# 10_RK3568_PowerGND.net
KiCad netlist of a schematic drawn in Altium Designer
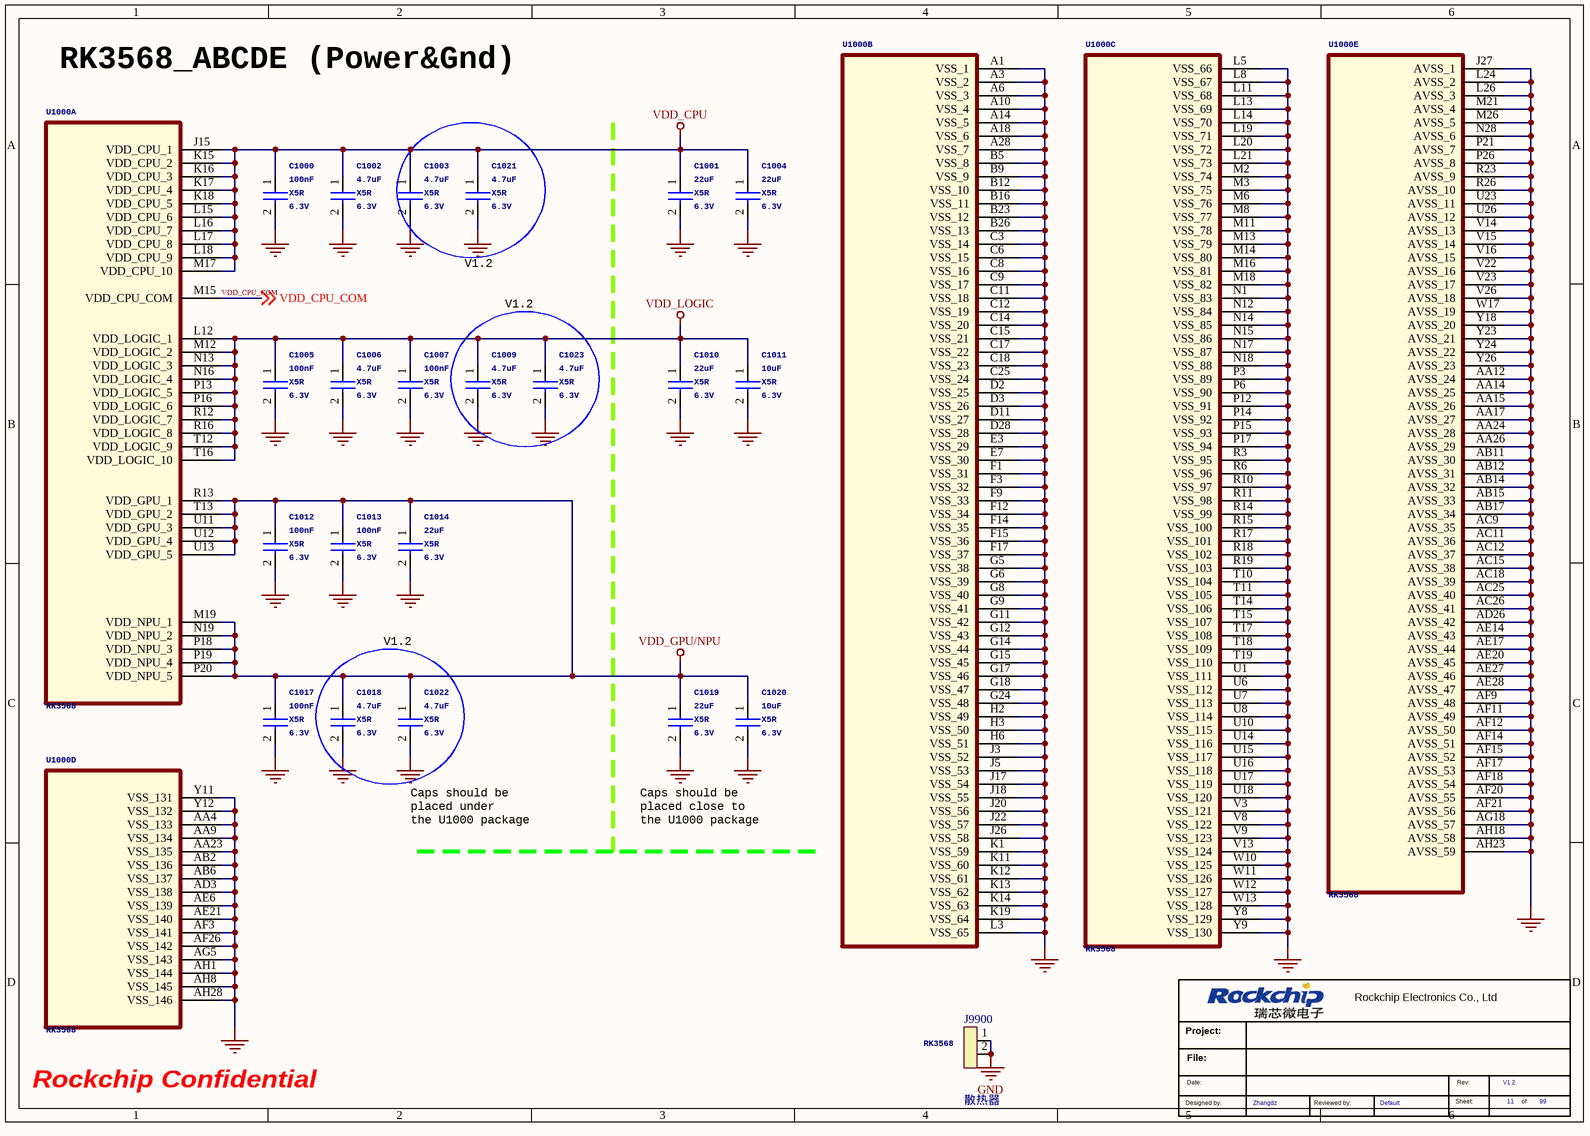
[diagram p0: 10.RK3568_PowerGND.SchDoc]

(export (version "E")
  (design (tool "Eeschema 10.0.6"))
  (components
    (comp (ref "*")
      (value "Rockchip_new")
      (fields
        (field (name "SCHEMATIC PAGE COUNT") "99")
        (field (name "SCHEMATIC PAGE NUMBER") "11")
        (field (name "DESIGNER") "Zhangdz")
        (field (name "REVISION") "V1.2")
        (field (name "CHECK") "Default")
      )
      (libsource (lib "*") (part "Rockchip_new"))
    )
    (comp (ref "C1000")
      (value "100nF")
      (footprint "C0201")
      (description "cap,100.00nF,+/-10%,6.3V,X5R,C0201")
      (fields
        (field (name "VOLTAGE") "6.3V")
        (field (name "DIELECTRIC") "X5R")
        (field (name "TOLERANCE") "10%")
        (field (name "MANUFACTURER") "TDK")
        (field (name "CREATED BY") "JJJ")
      )
      (libsource (lib "*") (part "CAP NP"))
    )
    (comp (ref "C1001")
      (value "22uF")
      (footprint "C0603")
      (description "cap,22.00uF,+/-20%,6.3V,X5R,C0603")
      (fields
        (field (name "VOLTAGE") "6.3V")
        (field (name "DIELECTRIC") "X5R")
        (field (name "TOLERANCE") "20%")
        (field (name "MANUFACTURER") "TDK")
        (field (name "CREATED BY") "JJJ")
      )
      (libsource (lib "*") (part "CAP NP"))
    )
    (comp (ref "C1002")
      (value "4.7uF")
      (footprint "C0402")
      (description "cap,4.70uF,+/-10%,6.3V,X5R,C0402")
      (fields
        (field (name "VOLTAGE") "6.3V")
        (field (name "DIELECTRIC") "X5R")
        (field (name "MANUFACTURER") "TDK")
        (field (name "TOLERANCE") "10%")
        (field (name "CREATED BY") "JJJ")
      )
      (libsource (lib "*") (part "CAP NP"))
    )
    (comp (ref "C1003")
      (value "4.7uF")
      (footprint "C0402")
      (description "cap,4.70uF,+/-10%,6.3V,X5R,C0402")
      (fields
        (field (name "VOLTAGE") "6.3V")
        (field (name "DIELECTRIC") "X5R")
        (field (name "MANUFACTURER") "TDK")
        (field (name "TOLERANCE") "10%")
        (field (name "CREATED BY") "JJJ")
      )
      (libsource (lib "*") (part "CAP NP"))
    )
    (comp (ref "C1004")
      (value "22uF")
      (footprint "C0603")
      (description "cap,22.00uF,+/-20%,6.3V,X5R,C0603")
      (fields
        (field (name "VOLTAGE") "6.3V")
        (field (name "DIELECTRIC") "X5R")
        (field (name "TOLERANCE") "20%")
        (field (name "MANUFACTURER") "TDK")
        (field (name "CREATED BY") "JJJ")
      )
      (libsource (lib "*") (part "CAP NP"))
    )
    (comp (ref "C1005")
      (value "100nF")
      (footprint "C0201")
      (description "cap,100.00nF,+/-10%,6.3V,X5R,C0201")
      (fields
        (field (name "VOLTAGE") "6.3V")
        (field (name "DIELECTRIC") "X5R")
        (field (name "TOLERANCE") "10%")
        (field (name "MANUFACTURER") "TDK")
        (field (name "CREATED BY") "JJJ")
      )
      (libsource (lib "*") (part "CAP NP"))
    )
    (comp (ref "C1006")
      (value "4.7uF")
      (footprint "C0402")
      (description "cap,4.70uF,+/-10%,6.3V,X5R,C0402")
      (fields
        (field (name "VOLTAGE") "6.3V")
        (field (name "DIELECTRIC") "X5R")
        (field (name "MANUFACTURER") "TDK")
        (field (name "TOLERANCE") "10%")
        (field (name "CREATED BY") "JJJ")
      )
      (libsource (lib "*") (part "CAP NP"))
    )
    (comp (ref "C1007")
      (value "100nF")
      (footprint "C0201")
      (description "cap,100.00nF,+/-10%,6.3V,X5R,C0201")
      (fields
        (field (name "VOLTAGE") "6.3V")
        (field (name "DIELECTRIC") "X5R")
        (field (name "TOLERANCE") "10%")
        (field (name "MANUFACTURER") "TDK")
        (field (name "CREATED BY") "JJJ")
      )
      (libsource (lib "*") (part "CAP NP"))
    )
    (comp (ref "C1009")
      (value "4.7uF")
      (footprint "C0402")
      (description "cap,4.70uF,+/-10%,6.3V,X5R,C0402")
      (fields
        (field (name "VOLTAGE") "6.3V")
        (field (name "DIELECTRIC") "X5R")
        (field (name "MANUFACTURER") "TDK")
        (field (name "TOLERANCE") "10%")
        (field (name "CREATED BY") "JJJ")
      )
      (libsource (lib "*") (part "CAP NP"))
    )
    (comp (ref "C1010")
      (value "22uF")
      (footprint "C0603")
      (description "cap,22.00uF,+/-20%,6.3V,X5R,C0603")
      (fields
        (field (name "VOLTAGE") "6.3V")
        (field (name "DIELECTRIC") "X5R")
        (field (name "MANUFACTURER") "TDK")
        (field (name "TOLERANCE") "20%")
        (field (name "CREATED BY") "JJJ")
      )
      (libsource (lib "*") (part "CAP NP"))
    )
    (comp (ref "C1011")
      (value "10uF")
      (footprint "C0603")
      (description "cap,10.00uF,+/-10%,6.3V,X5R,C0603")
      (fields
        (field (name "VOLTAGE") "6.3V")
        (field (name "DIELECTRIC") "X5R")
        (field (name "MANUFACTURER") "TDK")
        (field (name "TOLERANCE") "10%")
        (field (name "CREATED BY") "JJJ")
      )
      (libsource (lib "*") (part "CAP NP"))
    )
    (comp (ref "C1012")
      (value "100nF")
      (footprint "C0201")
      (description "cap,100.00nF,+/-10%,6.3V,X5R,C0201")
      (fields
        (field (name "VOLTAGE") "6.3V")
        (field (name "DIELECTRIC") "X5R")
        (field (name "MANUFACTURER") "TDK")
        (field (name "TOLERANCE") "10%")
        (field (name "CREATED BY") "JJJ")
      )
      (libsource (lib "*") (part "CAP NP"))
    )
    (comp (ref "C1013")
      (value "100nF")
      (footprint "C0201")
      (description "cap,100.00nF,+/-10%,6.3V,X5R,C0201")
      (fields
        (field (name "VOLTAGE") "6.3V")
        (field (name "DIELECTRIC") "X5R")
        (field (name "TOLERANCE") "10%")
        (field (name "MANUFACTURER") "TDK")
        (field (name "CREATED BY") "JJJ")
      )
      (libsource (lib "*") (part "CAP NP"))
    )
    (comp (ref "C1014")
      (value "22uF")
      (footprint "C0603")
      (description "cap,22.00uF,+/-20%,6.3V,X5R,C0603")
      (fields
        (field (name "VOLTAGE") "6.3V")
        (field (name "DIELECTRIC") "X5R")
        (field (name "MANUFACTURER") "TDK")
        (field (name "TOLERANCE") "20%")
        (field (name "CREATED BY") "JJJ")
      )
      (libsource (lib "*") (part "CAP NP"))
    )
    (comp (ref "C1017")
      (value "100nF")
      (footprint "C0201")
      (description "cap,100.00nF,+/-10%,6.3V,X5R,C0201")
      (fields
        (field (name "VOLTAGE") "6.3V")
        (field (name "DIELECTRIC") "X5R")
        (field (name "MANUFACTURER") "TDK")
        (field (name "TOLERANCE") "10%")
        (field (name "CREATED BY") "JJJ")
      )
      (libsource (lib "*") (part "CAP NP"))
    )
    (comp (ref "C1018")
      (value "4.7uF")
      (footprint "C0402")
      (description "cap,4.70uF,+/-10%,6.3V,X5R,C0402")
      (fields
        (field (name "VOLTAGE") "6.3V")
        (field (name "DIELECTRIC") "X5R")
        (field (name "TOLERANCE") "10%")
        (field (name "MANUFACTURER") "TDK")
        (field (name "CREATED BY") "JJJ")
      )
      (libsource (lib "*") (part "CAP NP"))
    )
    (comp (ref "C1019")
      (value "22uF")
      (footprint "C0603")
      (description "cap,22.00uF,+/-20%,6.3V,X5R,C0603")
      (fields
        (field (name "VOLTAGE") "6.3V")
        (field (name "DIELECTRIC") "X5R")
        (field (name "MANUFACTURER") "TDK")
        (field (name "TOLERANCE") "20%")
        (field (name "CREATED BY") "JJJ")
      )
      (libsource (lib "*") (part "CAP NP"))
    )
    (comp (ref "C1020")
      (value "10uF")
      (footprint "C0603")
      (description "cap,10.00uF,+/-10%,6.3V,X5R,C0603")
      (fields
        (field (name "VOLTAGE") "6.3V")
        (field (name "DIELECTRIC") "X5R")
        (field (name "MANUFACTURER") "TDK")
        (field (name "TOLERANCE") "10%")
        (field (name "CREATED BY") "JJJ")
      )
      (libsource (lib "*") (part "CAP NP"))
    )
    (comp (ref "C1021")
      (value "4.7uF")
      (footprint "C0402")
      (description "cap,4.70uF,+/-10%,6.3V,X5R,C0402")
      (fields
        (field (name "VOLTAGE") "6.3V")
        (field (name "DIELECTRIC") "X5R")
        (field (name "MANUFACTURER") "TDK")
        (field (name "TOLERANCE") "10%")
        (field (name "CREATED BY") "JJJ")
      )
      (libsource (lib "*") (part "CAP NP"))
    )
    (comp (ref "C1022")
      (value "4.7uF")
      (footprint "C0402")
      (description "cap,4.70uF,+/-10%,6.3V,X5R,C0402")
      (fields
        (field (name "VOLTAGE") "6.3V")
        (field (name "DIELECTRIC") "X5R")
        (field (name "TOLERANCE") "10%")
        (field (name "MANUFACTURER") "TDK")
        (field (name "CREATED BY") "JJJ")
      )
      (libsource (lib "*") (part "CAP NP"))
    )
    (comp (ref "C1023")
      (value "4.7uF")
      (footprint "C0402")
      (description "cap,4.70uF,+/-10%,6.3V,X5R,C0402")
      (fields
        (field (name "VOLTAGE") "6.3V")
        (field (name "DIELECTRIC") "X5R")
        (field (name "MANUFACTURER") "TDK")
        (field (name "TOLERANCE") "10%")
        (field (name "CREATED BY") "JJJ")
      )
      (libsource (lib "*") (part "CAP NP"))
    )
    (comp (ref "J9900")
      (value "散热器")
      (footprint "RADIATOR_38RX38RX10R")
      (description "SOCKET")
      (libsource (lib "模拟器件") (part "CON2"))
    )
    (comp (ref "U1000")
      (value "RK3568")
      (footprint "BGA636_19R00X19R00X1R20")
      (description "ROCKCHIP SOC")
      (fields (field (name "MANUFACTURER") "Rockchip (瑞芯微)") (field (name "CREATED BY") "JJJ"))
      (libsource (lib "*") (part "SOC_RK3568"))
    )
  )
  (nets
    (net (code "1") (name "GND") (class "Default")
      (node (ref "C1000") (pin "2") (pinfunction "2_2") (pintype "passive"))
      (node (ref "C1001") (pin "2") (pinfunction "2_2") (pintype "passive"))
      (node (ref "C1002") (pin "2") (pinfunction "2_2") (pintype "passive"))
      (node (ref "C1003") (pin "2") (pinfunction "2_2") (pintype "passive"))
      (node (ref "C1004") (pin "2") (pinfunction "2_2") (pintype "passive"))
      (node (ref "C1005") (pin "2") (pinfunction "2_2") (pintype "passive"))
      (node (ref "C1006") (pin "2") (pinfunction "2_2") (pintype "passive"))
      (node (ref "C1007") (pin "2") (pinfunction "2_2") (pintype "passive"))
      (node (ref "C1009") (pin "2") (pinfunction "2_2") (pintype "passive"))
      (node (ref "C1010") (pin "2") (pinfunction "2_2") (pintype "passive"))
      (node (ref "C1011") (pin "2") (pinfunction "2_2") (pintype "passive"))
      (node (ref "C1012") (pin "2") (pinfunction "2_2") (pintype "passive"))
      (node (ref "C1013") (pin "2") (pinfunction "2_2") (pintype "passive"))
      (node (ref "C1014") (pin "2") (pinfunction "2_2") (pintype "passive"))
      (node (ref "C1017") (pin "2") (pinfunction "2_2") (pintype "passive"))
      (node (ref "C1018") (pin "2") (pinfunction "2_2") (pintype "passive"))
      (node (ref "C1019") (pin "2") (pinfunction "2_2") (pintype "passive"))
      (node (ref "C1020") (pin "2") (pinfunction "2_2") (pintype "passive"))
      (node (ref "C1021") (pin "2") (pinfunction "2_2") (pintype "passive"))
      (node (ref "C1022") (pin "2") (pinfunction "2_2") (pintype "passive"))
      (node (ref "C1023") (pin "2") (pinfunction "2_2") (pintype "passive"))
      (node (ref "J9900") (pin "1") (pinfunction "1_1") (pintype "passive"))
      (node (ref "J9900") (pin "2") (pinfunction "2_2") (pintype "passive"))
      (node (ref "U1000") (pin "A1") (pinfunction "VSS_1_A1") (pintype "passive"))
      (node (ref "U1000") (pin "A10") (pinfunction "VSS_4_A10") (pintype "passive"))
      (node (ref "U1000") (pin "A14") (pinfunction "VSS_5_A14") (pintype "passive"))
      (node (ref "U1000") (pin "A18") (pinfunction "VSS_6_A18") (pintype "passive"))
      (node (ref "U1000") (pin "A28") (pinfunction "VSS_7_A28") (pintype "passive"))
      (node (ref "U1000") (pin "A3") (pinfunction "VSS_2_A3") (pintype "passive"))
      (node (ref "U1000") (pin "A6") (pinfunction "VSS_3_A6") (pintype "passive"))
      (node (ref "U1000") (pin "AA12") (pinfunction "AVSS_24_AA12") (pintype "passive"))
      (node (ref "U1000") (pin "AA14") (pinfunction "AVSS_25_AA14") (pintype "passive"))
      (node (ref "U1000") (pin "AA15") (pinfunction "AVSS_26_AA15") (pintype "passive"))
      (node (ref "U1000") (pin "AA17") (pinfunction "AVSS_27_AA17") (pintype "passive"))
      (node (ref "U1000") (pin "AA23") (pinfunction "VSS_135_AA23") (pintype "passive"))
      (node (ref "U1000") (pin "AA24") (pinfunction "AVSS_28_AA24") (pintype "passive"))
      (node (ref "U1000") (pin "AA26") (pinfunction "AVSS_29_AA26") (pintype "passive"))
      (node (ref "U1000") (pin "AA4") (pinfunction "VSS_133_AA4") (pintype "passive"))
      (node (ref "U1000") (pin "AA9") (pinfunction "VSS_134_AA9") (pintype "passive"))
      (node (ref "U1000") (pin "AB11") (pinfunction "AVSS_30_AB11") (pintype "passive"))
      (node (ref "U1000") (pin "AB12") (pinfunction "AVSS_31_AB12") (pintype "passive"))
      (node (ref "U1000") (pin "AB14") (pinfunction "AVSS_32_AB14") (pintype "passive"))
      (node (ref "U1000") (pin "AB15") (pinfunction "AVSS_33_AB15") (pintype "passive"))
      (node (ref "U1000") (pin "AB17") (pinfunction "AVSS_34_AB17") (pintype "passive"))
      (node (ref "U1000") (pin "AB2") (pinfunction "VSS_136_AB2") (pintype "passive"))
      (node (ref "U1000") (pin "AB6") (pinfunction "VSS_137_AB6") (pintype "passive"))
      (node (ref "U1000") (pin "AC11") (pinfunction "AVSS_36_AC11") (pintype "passive"))
      (node (ref "U1000") (pin "AC12") (pinfunction "AVSS_37_AC12") (pintype "passive"))
      (node (ref "U1000") (pin "AC15") (pinfunction "AVSS_38_AC15") (pintype "passive"))
      (node (ref "U1000") (pin "AC18") (pinfunction "AVSS_39_AC18") (pintype "passive"))
      (node (ref "U1000") (pin "AC25") (pinfunction "AVSS_40_AC25") (pintype "passive"))
      (node (ref "U1000") (pin "AC26") (pinfunction "AVSS_41_AC26") (pintype "passive"))
      (node (ref "U1000") (pin "AC9") (pinfunction "AVSS_35_AC9") (pintype "passive"))
      (node (ref "U1000") (pin "AD26") (pinfunction "AVSS_42_AD26") (pintype "passive"))
      (node (ref "U1000") (pin "AD3") (pinfunction "VSS_138_AD3") (pintype "passive"))
      (node (ref "U1000") (pin "AE14") (pinfunction "AVSS_43_AE14") (pintype "passive"))
      (node (ref "U1000") (pin "AE17") (pinfunction "AVSS_44_AE17") (pintype "passive"))
      (node (ref "U1000") (pin "AE20") (pinfunction "AVSS_45_AE20") (pintype "passive"))
      (node (ref "U1000") (pin "AE21") (pinfunction "VSS_140_AE21") (pintype "passive"))
      (node (ref "U1000") (pin "AE27") (pinfunction "AVSS_46_AE27") (pintype "passive"))
      (node (ref "U1000") (pin "AE28") (pinfunction "AVSS_47_AE28") (pintype "passive"))
      (node (ref "U1000") (pin "AE6") (pinfunction "VSS_139_AE6") (pintype "passive"))
      (node (ref "U1000") (pin "AF11") (pinfunction "AVSS_49_AF11") (pintype "passive"))
      (node (ref "U1000") (pin "AF12") (pinfunction "AVSS_50_AF12") (pintype "passive"))
      (node (ref "U1000") (pin "AF14") (pinfunction "AVSS_51_AF14") (pintype "passive"))
      (node (ref "U1000") (pin "AF15") (pinfunction "AVSS_52_AF15") (pintype "passive"))
      (node (ref "U1000") (pin "AF17") (pinfunction "AVSS_53_AF17") (pintype "passive"))
      (node (ref "U1000") (pin "AF18") (pinfunction "AVSS_54_AF18") (pintype "passive"))
      (node (ref "U1000") (pin "AF20") (pinfunction "AVSS_55_AF20") (pintype "passive"))
      (node (ref "U1000") (pin "AF21") (pinfunction "AVSS_56_AF21") (pintype "passive"))
      (node (ref "U1000") (pin "AF26") (pinfunction "VSS_142_AF26") (pintype "passive"))
      (node (ref "U1000") (pin "AF3") (pinfunction "VSS_141_AF3") (pintype "passive"))
      (node (ref "U1000") (pin "AF9") (pinfunction "AVSS_48_AF9") (pintype "passive"))
      (node (ref "U1000") (pin "AG18") (pinfunction "AVSS_57_AG18") (pintype "passive"))
      (node (ref "U1000") (pin "AG5") (pinfunction "VSS_143_AG5") (pintype "passive"))
      (node (ref "U1000") (pin "AH1") (pinfunction "VSS_144_AH1") (pintype "passive"))
      (node (ref "U1000") (pin "AH18") (pinfunction "AVSS_58_AH18") (pintype "passive"))
      (node (ref "U1000") (pin "AH23") (pinfunction "AVSS_59_AH23") (pintype "passive"))
      (node (ref "U1000") (pin "AH28") (pinfunction "VSS_146_AH28") (pintype "passive"))
      (node (ref "U1000") (pin "AH8") (pinfunction "VSS_145_AH8") (pintype "passive"))
      (node (ref "U1000") (pin "B12") (pinfunction "VSS_10_B12") (pintype "passive"))
      (node (ref "U1000") (pin "B16") (pinfunction "VSS_11_B16") (pintype "passive"))
      (node (ref "U1000") (pin "B23") (pinfunction "VSS_12_B23") (pintype "passive"))
      (node (ref "U1000") (pin "B26") (pinfunction "VSS_13_B26") (pintype "passive"))
      (node (ref "U1000") (pin "B5") (pinfunction "VSS_8_B5") (pintype "passive"))
      (node (ref "U1000") (pin "B9") (pinfunction "VSS_9_B9") (pintype "passive"))
      (node (ref "U1000") (pin "C11") (pinfunction "VSS_18_C11") (pintype "passive"))
      (node (ref "U1000") (pin "C12") (pinfunction "VSS_19_C12") (pintype "passive"))
      (node (ref "U1000") (pin "C14") (pinfunction "VSS_20_C14") (pintype "passive"))
      (node (ref "U1000") (pin "C15") (pinfunction "VSS_21_C15") (pintype "passive"))
      (node (ref "U1000") (pin "C17") (pinfunction "VSS_22_C17") (pintype "passive"))
      (node (ref "U1000") (pin "C18") (pinfunction "VSS_23_C18") (pintype "passive"))
      (node (ref "U1000") (pin "C25") (pinfunction "VSS_24_C25") (pintype "passive"))
      (node (ref "U1000") (pin "C3") (pinfunction "VSS_14_C3") (pintype "passive"))
      (node (ref "U1000") (pin "C6") (pinfunction "VSS_15_C6") (pintype "passive"))
      (node (ref "U1000") (pin "C8") (pinfunction "VSS_16_C8") (pintype "passive"))
      (node (ref "U1000") (pin "C9") (pinfunction "VSS_17_C9") (pintype "passive"))
      (node (ref "U1000") (pin "D11") (pinfunction "VSS_27_D11") (pintype "passive"))
      (node (ref "U1000") (pin "D2") (pinfunction "VSS_25_D2") (pintype "passive"))
      (node (ref "U1000") (pin "D28") (pinfunction "VSS_28_D28") (pintype "passive"))
      (node (ref "U1000") (pin "D3") (pinfunction "VSS_26_D3") (pintype "passive"))
      (node (ref "U1000") (pin "E3") (pinfunction "VSS_29_E3") (pintype "passive"))
      (node (ref "U1000") (pin "E7") (pinfunction "VSS_30_E7") (pintype "passive"))
      (node (ref "U1000") (pin "F1") (pinfunction "VSS_31_F1") (pintype "passive"))
      (node (ref "U1000") (pin "F12") (pinfunction "VSS_34_F12") (pintype "passive"))
      (node (ref "U1000") (pin "F14") (pinfunction "VSS_35_F14") (pintype "passive"))
      (node (ref "U1000") (pin "F15") (pinfunction "VSS_36_F15") (pintype "passive"))
      (node (ref "U1000") (pin "F17") (pinfunction "VSS_37_F17") (pintype "passive"))
      (node (ref "U1000") (pin "F3") (pinfunction "VSS_32_F3") (pintype "passive"))
      (node (ref "U1000") (pin "F9") (pinfunction "VSS_33_F9") (pintype "passive"))
      (node (ref "U1000") (pin "G11") (pinfunction "VSS_42_G11") (pintype "passive"))
      (node (ref "U1000") (pin "G12") (pinfunction "VSS_43_G12") (pintype "passive"))
      (node (ref "U1000") (pin "G14") (pinfunction "VSS_44_G14") (pintype "passive"))
      (node (ref "U1000") (pin "G15") (pinfunction "VSS_45_G15") (pintype "passive"))
      (node (ref "U1000") (pin "G17") (pinfunction "VSS_46_G17") (pintype "passive"))
      (node (ref "U1000") (pin "G18") (pinfunction "VSS_47_G18") (pintype "passive"))
      (node (ref "U1000") (pin "G24") (pinfunction "VSS_48_G24") (pintype "passive"))
      (node (ref "U1000") (pin "G5") (pinfunction "VSS_38_G5") (pintype "passive"))
      (node (ref "U1000") (pin "G6") (pinfunction "VSS_39_G6") (pintype "passive"))
      (node (ref "U1000") (pin "G8") (pinfunction "VSS_40_G8") (pintype "passive"))
      (node (ref "U1000") (pin "G9") (pinfunction "VSS_41_G9") (pintype "passive"))
      (node (ref "U1000") (pin "H2") (pinfunction "VSS_49_H2") (pintype "passive"))
      (node (ref "U1000") (pin "H3") (pinfunction "VSS_50_H3") (pintype "passive"))
      (node (ref "U1000") (pin "H6") (pinfunction "VSS_51_H6") (pintype "passive"))
      (node (ref "U1000") (pin "J17") (pinfunction "VSS_54_J17") (pintype "passive"))
      (node (ref "U1000") (pin "J18") (pinfunction "VSS_55_J18") (pintype "passive"))
      (node (ref "U1000") (pin "J20") (pinfunction "VSS_56_J20") (pintype "passive"))
      (node (ref "U1000") (pin "J22") (pinfunction "VSS_57_J22") (pintype "passive"))
      (node (ref "U1000") (pin "J26") (pinfunction "VSS_58_J26") (pintype "passive"))
      (node (ref "U1000") (pin "J27") (pinfunction "AVSS_1_J27") (pintype "passive"))
      (node (ref "U1000") (pin "J3") (pinfunction "VSS_52_J3") (pintype "passive"))
      (node (ref "U1000") (pin "J5") (pinfunction "VSS_53_J5") (pintype "passive"))
      (node (ref "U1000") (pin "K1") (pinfunction "VSS_59_K1") (pintype "passive"))
      (node (ref "U1000") (pin "K11") (pinfunction "VSS_60_K11") (pintype "passive"))
      (node (ref "U1000") (pin "K12") (pinfunction "VSS_61_K12") (pintype "passive"))
      (node (ref "U1000") (pin "K13") (pinfunction "VSS_62_K13") (pintype "passive"))
      (node (ref "U1000") (pin "K14") (pinfunction "VSS_63_K14") (pintype "passive"))
      (node (ref "U1000") (pin "K19") (pinfunction "VSS_64_K19") (pintype "passive"))
      (node (ref "U1000") (pin "L11") (pinfunction "VSS_68_L11") (pintype "passive"))
      (node (ref "U1000") (pin "L13") (pinfunction "VSS_69_L13") (pintype "passive"))
      (node (ref "U1000") (pin "L14") (pinfunction "VSS_70_L14") (pintype "passive"))
      (node (ref "U1000") (pin "L19") (pinfunction "VSS_71_L19") (pintype "passive"))
      (node (ref "U1000") (pin "L20") (pinfunction "VSS_72_L20") (pintype "passive"))
      (node (ref "U1000") (pin "L21") (pinfunction "VSS_73_L21") (pintype "passive"))
      (node (ref "U1000") (pin "L24") (pinfunction "AVSS_2_L24") (pintype "passive"))
      (node (ref "U1000") (pin "L26") (pinfunction "AVSS_3_L26") (pintype "passive"))
      (node (ref "U1000") (pin "L3") (pinfunction "VSS_65_L3") (pintype "passive"))
      (node (ref "U1000") (pin "L5") (pinfunction "VSS_66_L5") (pintype "passive"))
      (node (ref "U1000") (pin "L8") (pinfunction "VSS_67_L8") (pintype "passive"))
      (node (ref "U1000") (pin "M11") (pinfunction "VSS_78_M11") (pintype "passive"))
      (node (ref "U1000") (pin "M13") (pinfunction "VSS_79_M13") (pintype "passive"))
      (node (ref "U1000") (pin "M14") (pinfunction "VSS_80_M14") (pintype "passive"))
      (node (ref "U1000") (pin "M16") (pinfunction "VSS_81_M16") (pintype "passive"))
      (node (ref "U1000") (pin "M18") (pinfunction "VSS_82_M18") (pintype "passive"))
      (node (ref "U1000") (pin "M2") (pinfunction "VSS_74_M2") (pintype "passive"))
      (node (ref "U1000") (pin "M21") (pinfunction "AVSS_4_M21") (pintype "passive"))
      (node (ref "U1000") (pin "M26") (pinfunction "AVSS_5_M26") (pintype "passive"))
      (node (ref "U1000") (pin "M3") (pinfunction "VSS_75_M3") (pintype "passive"))
      (node (ref "U1000") (pin "M6") (pinfunction "VSS_76_M6") (pintype "passive"))
      (node (ref "U1000") (pin "M8") (pinfunction "VSS_77_M8") (pintype "passive"))
      (node (ref "U1000") (pin "N1") (pinfunction "VSS_83_N1") (pintype "passive"))
      (node (ref "U1000") (pin "N12") (pinfunction "VSS_84_N12") (pintype "passive"))
      (node (ref "U1000") (pin "N14") (pinfunction "VSS_85_N14") (pintype "passive"))
      (node (ref "U1000") (pin "N15") (pinfunction "VSS_86_N15") (pintype "passive"))
      (node (ref "U1000") (pin "N17") (pinfunction "VSS_87_N17") (pintype "passive"))
      (node (ref "U1000") (pin "N18") (pinfunction "VSS_88_N18") (pintype "passive"))
      (node (ref "U1000") (pin "N28") (pinfunction "AVSS_6_N28") (pintype "passive"))
      (node (ref "U1000") (pin "P12") (pinfunction "VSS_91_P12") (pintype "passive"))
      (node (ref "U1000") (pin "P14") (pinfunction "VSS_92_P14") (pintype "passive"))
      (node (ref "U1000") (pin "P15") (pinfunction "VSS_93_P15") (pintype "passive"))
      (node (ref "U1000") (pin "P17") (pinfunction "VSS_94_P17") (pintype "passive"))
      (node (ref "U1000") (pin "P21") (pinfunction "AVSS_7_P21") (pintype "passive"))
      (node (ref "U1000") (pin "P26") (pinfunction "AVSS_8_P26") (pintype "passive"))
      (node (ref "U1000") (pin "P3") (pinfunction "VSS_89_P3") (pintype "passive"))
      (node (ref "U1000") (pin "P6") (pinfunction "VSS_90_P6") (pintype "passive"))
      (node (ref "U1000") (pin "R10") (pinfunction "VSS_97_R10") (pintype "passive"))
      (node (ref "U1000") (pin "R11") (pinfunction "VSS_98_R11") (pintype "passive"))
      (node (ref "U1000") (pin "R14") (pinfunction "VSS_99_R14") (pintype "passive"))
      (node (ref "U1000") (pin "R15") (pinfunction "VSS_100_R15") (pintype "passive"))
      (node (ref "U1000") (pin "R17") (pinfunction "VSS_101_R17") (pintype "passive"))
      (node (ref "U1000") (pin "R18") (pinfunction "VSS_102_R18") (pintype "passive"))
      (node (ref "U1000") (pin "R19") (pinfunction "VSS_103_R19") (pintype "passive"))
      (node (ref "U1000") (pin "R23") (pinfunction "AVSS_9_R23") (pintype "passive"))
      (node (ref "U1000") (pin "R26") (pinfunction "AVSS_10_R26") (pintype "passive"))
      (node (ref "U1000") (pin "R3") (pinfunction "VSS_95_R3") (pintype "passive"))
      (node (ref "U1000") (pin "R6") (pinfunction "VSS_96_R6") (pintype "passive"))
      (node (ref "U1000") (pin "T10") (pinfunction "VSS_104_T10") (pintype "passive"))
      (node (ref "U1000") (pin "T11") (pinfunction "VSS_105_T11") (pintype "passive"))
      (node (ref "U1000") (pin "T14") (pinfunction "VSS_106_T14") (pintype "passive"))
      (node (ref "U1000") (pin "T15") (pinfunction "VSS_107_T15") (pintype "passive"))
      (node (ref "U1000") (pin "T17") (pinfunction "VSS_108_T17") (pintype "passive"))
      (node (ref "U1000") (pin "T18") (pinfunction "VSS_109_T18") (pintype "passive"))
      (node (ref "U1000") (pin "T19") (pinfunction "VSS_110_T19") (pintype "passive"))
      (node (ref "U1000") (pin "U1") (pinfunction "VSS_111_U1") (pintype "passive"))
      (node (ref "U1000") (pin "U10") (pinfunction "VSS_115_U10") (pintype "passive"))
      (node (ref "U1000") (pin "U14") (pinfunction "VSS_116_U14") (pintype "passive"))
      (node (ref "U1000") (pin "U15") (pinfunction "VSS_117_U15") (pintype "passive"))
      (node (ref "U1000") (pin "U16") (pinfunction "VSS_118_U16") (pintype "passive"))
      (node (ref "U1000") (pin "U17") (pinfunction "VSS_119_U17") (pintype "passive"))
      (node (ref "U1000") (pin "U18") (pinfunction "VSS_120_U18") (pintype "passive"))
      (node (ref "U1000") (pin "U23") (pinfunction "AVSS_11_U23") (pintype "passive"))
      (node (ref "U1000") (pin "U26") (pinfunction "AVSS_12_U26") (pintype "passive"))
      (node (ref "U1000") (pin "U6") (pinfunction "VSS_112_U6") (pintype "passive"))
      (node (ref "U1000") (pin "U7") (pinfunction "VSS_113_U7") (pintype "passive"))
      (node (ref "U1000") (pin "U8") (pinfunction "VSS_114_U8") (pintype "passive"))
      (node (ref "U1000") (pin "V13") (pinfunction "VSS_124_V13") (pintype "passive"))
      (node (ref "U1000") (pin "V14") (pinfunction "AVSS_13_V14") (pintype "passive"))
      (node (ref "U1000") (pin "V15") (pinfunction "AVSS_14_V15") (pintype "passive"))
      (node (ref "U1000") (pin "V16") (pinfunction "AVSS_15_V16") (pintype "passive"))
      (node (ref "U1000") (pin "V22") (pinfunction "AVSS_16_V22") (pintype "passive"))
      (node (ref "U1000") (pin "V23") (pinfunction "AVSS_17_V23") (pintype "passive"))
      (node (ref "U1000") (pin "V26") (pinfunction "AVSS_18_V26") (pintype "passive"))
      (node (ref "U1000") (pin "V3") (pinfunction "VSS_121_V3") (pintype "passive"))
      (node (ref "U1000") (pin "V8") (pinfunction "VSS_122_V8") (pintype "passive"))
      (node (ref "U1000") (pin "V9") (pinfunction "VSS_123_V9") (pintype "passive"))
      (node (ref "U1000") (pin "W10") (pinfunction "VSS_125_W10") (pintype "passive"))
      (node (ref "U1000") (pin "W11") (pinfunction "VSS_126_W11") (pintype "passive"))
      (node (ref "U1000") (pin "W12") (pinfunction "VSS_127_W12") (pintype "passive"))
      (node (ref "U1000") (pin "W13") (pinfunction "VSS_128_W13") (pintype "passive"))
      (node (ref "U1000") (pin "W17") (pinfunction "AVSS_19_W17") (pintype "passive"))
      (node (ref "U1000") (pin "Y11") (pinfunction "VSS_131_Y11") (pintype "passive"))
      (node (ref "U1000") (pin "Y12") (pinfunction "VSS_132_Y12") (pintype "passive"))
      (node (ref "U1000") (pin "Y18") (pinfunction "AVSS_20_Y18") (pintype "passive"))
      (node (ref "U1000") (pin "Y23") (pinfunction "AVSS_21_Y23") (pintype "passive"))
      (node (ref "U1000") (pin "Y24") (pinfunction "AVSS_22_Y24") (pintype "passive"))
      (node (ref "U1000") (pin "Y26") (pinfunction "AVSS_23_Y26") (pintype "passive"))
      (node (ref "U1000") (pin "Y8") (pinfunction "VSS_129_Y8") (pintype "passive"))
      (node (ref "U1000") (pin "Y9") (pinfunction "VSS_130_Y9") (pintype "passive"))
    )
    (net (code "2") (name "VDD_CPU") (class "Default")
      (node (ref "C1000") (pin "1") (pinfunction "1_1") (pintype "passive"))
      (node (ref "C1001") (pin "1") (pinfunction "1_1") (pintype "passive"))
      (node (ref "C1002") (pin "1") (pinfunction "1_1") (pintype "passive"))
      (node (ref "C1003") (pin "1") (pinfunction "1_1") (pintype "passive"))
      (node (ref "C1004") (pin "1") (pinfunction "1_1") (pintype "passive"))
      (node (ref "C1021") (pin "1") (pinfunction "1_1") (pintype "passive"))
      (node (ref "U1000") (pin "J15") (pinfunction "VDD_CPU_1_J15") (pintype "passive"))
      (node (ref "U1000") (pin "K15") (pinfunction "VDD_CPU_2_K15") (pintype "passive"))
      (node (ref "U1000") (pin "K16") (pinfunction "VDD_CPU_3_K16") (pintype "passive"))
      (node (ref "U1000") (pin "K17") (pinfunction "VDD_CPU_4_K17") (pintype "passive"))
      (node (ref "U1000") (pin "K18") (pinfunction "VDD_CPU_5_K18") (pintype "passive"))
      (node (ref "U1000") (pin "L15") (pinfunction "VDD_CPU_6_L15") (pintype "passive"))
      (node (ref "U1000") (pin "L16") (pinfunction "VDD_CPU_7_L16") (pintype "passive"))
      (node (ref "U1000") (pin "L17") (pinfunction "VDD_CPU_8_L17") (pintype "passive"))
      (node (ref "U1000") (pin "L18") (pinfunction "VDD_CPU_9_L18") (pintype "passive"))
      (node (ref "U1000") (pin "M17") (pinfunction "VDD_CPU_10_M17") (pintype "passive"))
    )
    (net (code "3") (name "VDD_CPU_COM") (class "Default")
      (node (ref "U1000") (pin "M15") (pinfunction "VDD_CPU_COM_M15") (pintype "passive"))
    )
    (net (code "4") (name "VDD_GPU{slash}NPU") (class "Default")
      (node (ref "C1012") (pin "1") (pinfunction "1_1") (pintype "passive"))
      (node (ref "C1013") (pin "1") (pinfunction "1_1") (pintype "passive"))
      (node (ref "C1014") (pin "1") (pinfunction "1_1") (pintype "passive"))
      (node (ref "C1017") (pin "1") (pinfunction "1_1") (pintype "passive"))
      (node (ref "C1018") (pin "1") (pinfunction "1_1") (pintype "passive"))
      (node (ref "C1019") (pin "1") (pinfunction "1_1") (pintype "passive"))
      (node (ref "C1020") (pin "1") (pinfunction "1_1") (pintype "passive"))
      (node (ref "C1022") (pin "1") (pinfunction "1_1") (pintype "passive"))
      (node (ref "U1000") (pin "M19") (pinfunction "VDD_NPU_1_M19") (pintype "passive"))
      (node (ref "U1000") (pin "N19") (pinfunction "VDD_NPU_2_N19") (pintype "passive"))
      (node (ref "U1000") (pin "P18") (pinfunction "VDD_NPU_3_P18") (pintype "passive"))
      (node (ref "U1000") (pin "P19") (pinfunction "VDD_NPU_4_P19") (pintype "passive"))
      (node (ref "U1000") (pin "P20") (pinfunction "VDD_NPU_5_P20") (pintype "passive"))
      (node (ref "U1000") (pin "R13") (pinfunction "VDD_GPU_1_R13") (pintype "passive"))
      (node (ref "U1000") (pin "T13") (pinfunction "VDD_GPU_2_T13") (pintype "passive"))
      (node (ref "U1000") (pin "U11") (pinfunction "VDD_GPU_3_U11") (pintype "passive"))
      (node (ref "U1000") (pin "U12") (pinfunction "VDD_GPU_4_U12") (pintype "passive"))
      (node (ref "U1000") (pin "U13") (pinfunction "VDD_GPU_5_U13") (pintype "passive"))
    )
    (net (code "5") (name "VDD_LOGIC") (class "Default")
      (node (ref "C1005") (pin "1") (pinfunction "1_1") (pintype "passive"))
      (node (ref "C1006") (pin "1") (pinfunction "1_1") (pintype "passive"))
      (node (ref "C1007") (pin "1") (pinfunction "1_1") (pintype "passive"))
      (node (ref "C1009") (pin "1") (pinfunction "1_1") (pintype "passive"))
      (node (ref "C1010") (pin "1") (pinfunction "1_1") (pintype "passive"))
      (node (ref "C1011") (pin "1") (pinfunction "1_1") (pintype "passive"))
      (node (ref "C1023") (pin "1") (pinfunction "1_1") (pintype "passive"))
      (node (ref "U1000") (pin "L12") (pinfunction "VDD_LOGIC_1_L12") (pintype "passive"))
      (node (ref "U1000") (pin "M12") (pinfunction "VDD_LOGIC_2_M12") (pintype "passive"))
      (node (ref "U1000") (pin "N13") (pinfunction "VDD_LOGIC_3_N13") (pintype "passive"))
      (node (ref "U1000") (pin "N16") (pinfunction "VDD_LOGIC_4_N16") (pintype "passive"))
      (node (ref "U1000") (pin "P13") (pinfunction "VDD_LOGIC_5_P13") (pintype "passive"))
      (node (ref "U1000") (pin "P16") (pinfunction "VDD_LOGIC_6_P16") (pintype "passive"))
      (node (ref "U1000") (pin "R12") (pinfunction "VDD_LOGIC_7_R12") (pintype "passive"))
      (node (ref "U1000") (pin "R16") (pinfunction "VDD_LOGIC_8_R16") (pintype "passive"))
      (node (ref "U1000") (pin "T12") (pinfunction "VDD_LOGIC_9_T12") (pintype "passive"))
      (node (ref "U1000") (pin "T16") (pinfunction "VDD_LOGIC_10_T16") (pintype "passive"))
    )
  )
)
